# preamp.net
KiCad netlist of a schematic drawn in Altium Designer
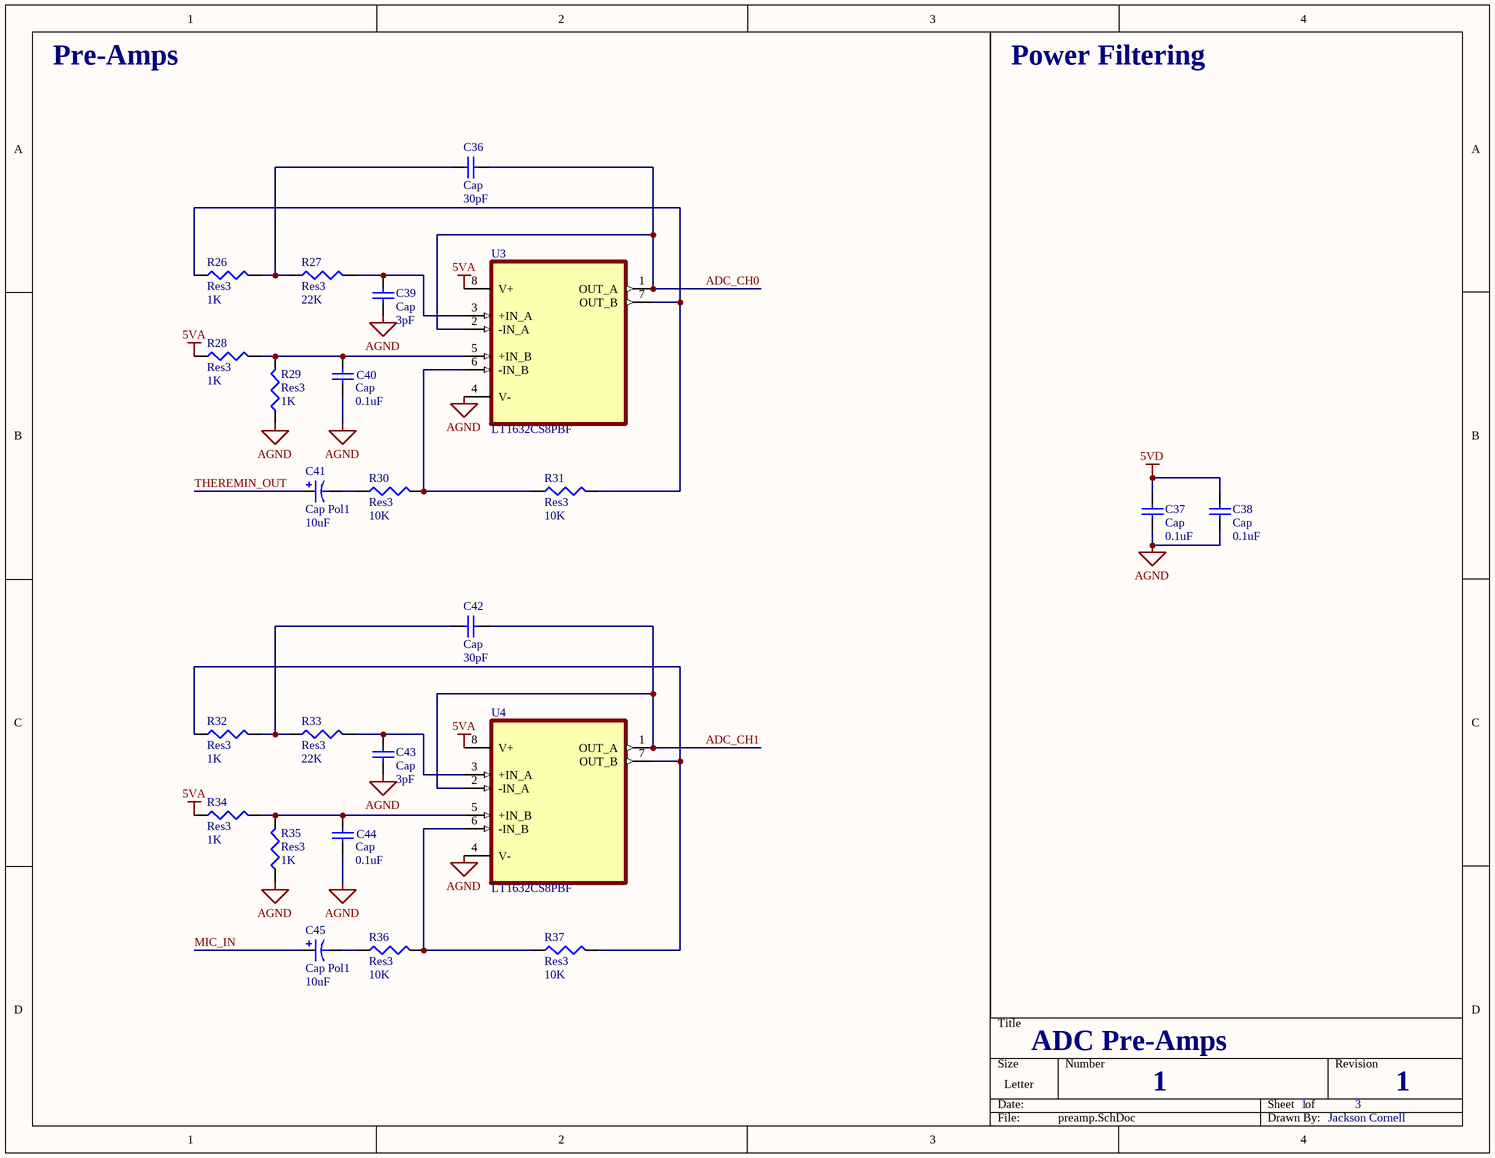
[diagram p0: preamp.SchDoc]

(export (version "E")
  (design (tool "Eeschema 10.0.6"))
  (components
    (comp (ref "C36")
      (value "Cap")
      (footprint "CAPC0805")
      (description "Capacitor")
      (fields (field (name "ALTIUM_VALUE") "30pF") (field (name "PUBLISHER") "Altium Limited"))
      (libsource (lib "Miscellaneous Devices") (part "Cap"))
    )
    (comp (ref "C37")
      (value "Cap")
      (footprint "CAPC0805")
      (description "Capacitor")
      (fields (field (name "ALTIUM_VALUE") "0.1uF") (field (name "PUBLISHER") "Altium Limited"))
      (libsource (lib "Miscellaneous Devices") (part "Cap"))
    )
    (comp (ref "C38")
      (value "Cap")
      (footprint "CAPC0805")
      (description "Capacitor")
      (fields (field (name "ALTIUM_VALUE") "0.1uF") (field (name "PUBLISHER") "Altium Limited"))
      (libsource (lib "Miscellaneous Devices") (part "Cap"))
    )
    (comp (ref "C39")
      (value "Cap")
      (footprint "CAPC0805")
      (description "Capacitor")
      (fields (field (name "ALTIUM_VALUE") "3pF") (field (name "PUBLISHER") "Altium Limited"))
      (libsource (lib "Miscellaneous Devices") (part "Cap"))
    )
    (comp (ref "C40")
      (value "Cap")
      (footprint "CAPC0805")
      (description "Capacitor")
      (fields (field (name "ALTIUM_VALUE") "0.1uF") (field (name "PUBLISHER") "Altium Limited"))
      (libsource (lib "Miscellaneous Devices") (part "Cap"))
    )
    (comp (ref "C41")
      (value "Cap Pol1")
      (footprint "CAPC0805")
      (description "Polarized Capacitor (Radial)")
      (fields (field (name "ALTIUM_VALUE") "10uF") (field (name "PUBLISHER") "Altium Limited"))
      (libsource (lib "Miscellaneous Devices") (part "Cap Pol1"))
    )
    (comp (ref "C42")
      (value "Cap")
      (footprint "CAPC0805")
      (description "Capacitor")
      (fields (field (name "ALTIUM_VALUE") "30pF") (field (name "PUBLISHER") "Altium Limited"))
      (libsource (lib "Miscellaneous Devices") (part "Cap"))
    )
    (comp (ref "C43")
      (value "Cap")
      (footprint "CAPC0805")
      (description "Capacitor")
      (fields (field (name "ALTIUM_VALUE") "3pF") (field (name "PUBLISHER") "Altium Limited"))
      (libsource (lib "Miscellaneous Devices") (part "Cap"))
    )
    (comp (ref "C44")
      (value "Cap")
      (footprint "CAPC0805")
      (description "Capacitor")
      (fields (field (name "ALTIUM_VALUE") "0.1uF") (field (name "PUBLISHER") "Altium Limited"))
      (libsource (lib "Miscellaneous Devices") (part "Cap"))
    )
    (comp (ref "C45")
      (value "Cap Pol1")
      (footprint "RES0805")
      (description "Polarized Capacitor (Radial)")
      (fields (field (name "ALTIUM_VALUE") "10uF") (field (name "PUBLISHER") "Altium Limited"))
      (libsource (lib "Miscellaneous Devices") (part "Cap Pol1"))
    )
    (comp (ref "R26")
      (value "Res3")
      (footprint "RES0805")
      (description "Resistor")
      (fields (field (name "ALTIUM_VALUE") "1K") (field (name "PUBLISHER") "Altium Limited"))
      (libsource (lib "Miscellaneous Devices") (part "Res3"))
    )
    (comp (ref "R27")
      (value "Res3")
      (footprint "RES0805")
      (description "Resistor")
      (fields (field (name "ALTIUM_VALUE") "22K") (field (name "PUBLISHER") "Altium Limited"))
      (libsource (lib "Miscellaneous Devices") (part "Res3"))
    )
    (comp (ref "R28")
      (value "Res3")
      (footprint "RES0805")
      (description "Resistor")
      (fields (field (name "ALTIUM_VALUE") "1K") (field (name "PUBLISHER") "Altium Limited"))
      (libsource (lib "Miscellaneous Devices") (part "Res3"))
    )
    (comp (ref "R29")
      (value "Res3")
      (footprint "RES0805")
      (description "Resistor")
      (fields (field (name "ALTIUM_VALUE") "1K") (field (name "PUBLISHER") "Altium Limited"))
      (libsource (lib "Miscellaneous Devices") (part "Res3"))
    )
    (comp (ref "R30")
      (value "Res3")
      (footprint "RES0805")
      (description "Resistor")
      (fields (field (name "ALTIUM_VALUE") "10K") (field (name "PUBLISHER") "Altium Limited"))
      (libsource (lib "Miscellaneous Devices") (part "Res3"))
    )
    (comp (ref "R31")
      (value "Res3")
      (footprint "RES0805")
      (description "Resistor")
      (fields (field (name "ALTIUM_VALUE") "10K") (field (name "PUBLISHER") "Altium Limited"))
      (libsource (lib "Miscellaneous Devices") (part "Res3"))
    )
    (comp (ref "R32")
      (value "Res3")
      (footprint "RES0805")
      (description "Resistor")
      (fields (field (name "ALTIUM_VALUE") "1K") (field (name "PUBLISHER") "Altium Limited"))
      (libsource (lib "Miscellaneous Devices") (part "Res3"))
    )
    (comp (ref "R33")
      (value "Res3")
      (footprint "RES0805")
      (description "Resistor")
      (fields (field (name "ALTIUM_VALUE") "22K") (field (name "PUBLISHER") "Altium Limited"))
      (libsource (lib "Miscellaneous Devices") (part "Res3"))
    )
    (comp (ref "R34")
      (value "Res3")
      (footprint "RES0805")
      (description "Resistor")
      (fields (field (name "ALTIUM_VALUE") "1K") (field (name "PUBLISHER") "Altium Limited"))
      (libsource (lib "Miscellaneous Devices") (part "Res3"))
    )
    (comp (ref "R35")
      (value "Res3")
      (footprint "RES0805")
      (description "Resistor")
      (fields (field (name "ALTIUM_VALUE") "1K") (field (name "PUBLISHER") "Altium Limited"))
      (libsource (lib "Miscellaneous Devices") (part "Res3"))
    )
    (comp (ref "R36")
      (value "Res3")
      (footprint "RES0805")
      (description "Resistor")
      (fields (field (name "ALTIUM_VALUE") "10K") (field (name "PUBLISHER") "Altium Limited"))
      (libsource (lib "Miscellaneous Devices") (part "Res3"))
    )
    (comp (ref "R37")
      (value "Res3")
      (footprint "RES0805")
      (description "Resistor")
      (fields (field (name "ALTIUM_VALUE") "10K") (field (name "PUBLISHER") "Altium Limited"))
      (libsource (lib "Miscellaneous Devices") (part "Res3"))
    )
    (comp (ref "U3")
      (value "LT1632CS8PBF")
      (footprint "SOIC127P600X175-8N")
      (description "45MHz, 45V/ms, Dual/Quad Rail-to-Rail Input and Output  Precision Op Amps")
      (libsource (lib "LT1632CS8PBF") (part "LT1632CS8PBF"))
    )
    (comp (ref "U4")
      (value "LT1632CS8PBF")
      (footprint "SOIC127P600X175-8N")
      (description "45MHz, 45V/ms, Dual/Quad Rail-to-Rail Input and Output  Precision Op Amps")
      (libsource (lib "LT1632CS8PBF") (part "LT1632CS8PBF"))
    )
  )
  (nets
    (net (code "1") (name "/ADC_CH0") (class "Default")
      (node (ref "C36") (pin "2") (pinfunction "2_2") (pintype "passive"))
      (node (ref "U3") (pin "1") (pinfunction "OUT_A_1") (pintype "output"))
      (node (ref "U3") (pin "2") (pinfunction "-IN_A_2") (pintype "input"))
    )
    (net (code "2") (name "/ADC_CH1") (class "Default")
      (node (ref "C42") (pin "2") (pinfunction "2_2") (pintype "passive"))
      (node (ref "U4") (pin "1") (pinfunction "OUT_A_1") (pintype "output"))
      (node (ref "U4") (pin "2") (pinfunction "-IN_A_2") (pintype "input"))
    )
    (net (code "3") (name "/MIC_IN") (class "Default")
      (node (ref "C45") (pin "1") (pinfunction "1_1") (pintype "passive"))
    )
    (net (code "4") (name "/THEREMIN_OUT") (class "Default")
      (node (ref "C41") (pin "1") (pinfunction "1_1") (pintype "passive"))
    )
    (net (code "5") (name "5VA") (class "Default")
      (node (ref "R28") (pin "1") (pinfunction "1_1") (pintype "passive"))
      (node (ref "R34") (pin "1") (pinfunction "1_1") (pintype "passive"))
      (node (ref "U3") (pin "8") (pinfunction "V+_8") (pintype "power_in"))
      (node (ref "U4") (pin "8") (pinfunction "V+_8") (pintype "power_in"))
    )
    (net (code "6") (name "5VD") (class "Default")
      (node (ref "C37") (pin "2") (pinfunction "2_2") (pintype "passive"))
      (node (ref "C38") (pin "2") (pinfunction "2_2") (pintype "passive"))
    )
    (net (code "7") (name "AGND") (class "Default")
      (node (ref "C37") (pin "1") (pinfunction "1_1") (pintype "passive"))
      (node (ref "C38") (pin "1") (pinfunction "1_1") (pintype "passive"))
      (node (ref "C39") (pin "1") (pinfunction "1_1") (pintype "passive"))
      (node (ref "C40") (pin "1") (pinfunction "1_1") (pintype "passive"))
      (node (ref "C43") (pin "1") (pinfunction "1_1") (pintype "passive"))
      (node (ref "C44") (pin "1") (pinfunction "1_1") (pintype "passive"))
      (node (ref "R29") (pin "1") (pinfunction "1_1") (pintype "passive"))
      (node (ref "R35") (pin "1") (pinfunction "1_1") (pintype "passive"))
      (node (ref "U3") (pin "4") (pinfunction "V-_4") (pintype "power_in"))
      (node (ref "U4") (pin "4") (pinfunction "V-_4") (pintype "power_in"))
    )
    (net (code "8") (name "Net-(C36-Pad1)") (class "Default")
      (node (ref "C36") (pin "1") (pinfunction "1_1") (pintype "passive"))
      (node (ref "R26") (pin "2") (pinfunction "2_2") (pintype "passive"))
      (node (ref "R27") (pin "1") (pinfunction "1_1") (pintype "passive"))
    )
    (net (code "9") (name "Net-(C41-Pad2)") (class "Default")
      (node (ref "C41") (pin "2") (pinfunction "2_2") (pintype "passive"))
      (node (ref "R30") (pin "1") (pinfunction "1_1") (pintype "passive"))
    )
    (net (code "10") (name "Net-(C42-Pad1)") (class "Default")
      (node (ref "C42") (pin "1") (pinfunction "1_1") (pintype "passive"))
      (node (ref "R32") (pin "2") (pinfunction "2_2") (pintype "passive"))
      (node (ref "R33") (pin "1") (pinfunction "1_1") (pintype "passive"))
    )
    (net (code "11") (name "Net-(C45-Pad2)") (class "Default")
      (node (ref "C45") (pin "2") (pinfunction "2_2") (pintype "passive"))
      (node (ref "R36") (pin "1") (pinfunction "1_1") (pintype "passive"))
    )
    (net (code "12") (name "Net-(U3-+IN_A)") (class "Default")
      (node (ref "C39") (pin "2") (pinfunction "2_2") (pintype "passive"))
      (node (ref "R27") (pin "2") (pinfunction "2_2") (pintype "passive"))
      (node (ref "U3") (pin "3") (pinfunction "+IN_A_3") (pintype "input"))
    )
    (net (code "13") (name "Net-(U3-+IN_B)") (class "Default")
      (node (ref "C40") (pin "2") (pinfunction "2_2") (pintype "passive"))
      (node (ref "R28") (pin "2") (pinfunction "2_2") (pintype "passive"))
      (node (ref "R29") (pin "2") (pinfunction "2_2") (pintype "passive"))
      (node (ref "U3") (pin "5") (pinfunction "+IN_B_5") (pintype "input"))
    )
    (net (code "14") (name "Net-(U3--IN_B)") (class "Default")
      (node (ref "R30") (pin "2") (pinfunction "2_2") (pintype "passive"))
      (node (ref "R31") (pin "1") (pinfunction "1_1") (pintype "passive"))
      (node (ref "U3") (pin "6") (pinfunction "-IN_B_6") (pintype "input"))
    )
    (net (code "15") (name "Net-(U3-OUT_B)") (class "Default")
      (node (ref "R26") (pin "1") (pinfunction "1_1") (pintype "passive"))
      (node (ref "R31") (pin "2") (pinfunction "2_2") (pintype "passive"))
      (node (ref "U3") (pin "7") (pinfunction "OUT_B_7") (pintype "output"))
    )
    (net (code "16") (name "Net-(U4-+IN_A)") (class "Default")
      (node (ref "C43") (pin "2") (pinfunction "2_2") (pintype "passive"))
      (node (ref "R33") (pin "2") (pinfunction "2_2") (pintype "passive"))
      (node (ref "U4") (pin "3") (pinfunction "+IN_A_3") (pintype "input"))
    )
    (net (code "17") (name "Net-(U4-+IN_B)") (class "Default")
      (node (ref "C44") (pin "2") (pinfunction "2_2") (pintype "passive"))
      (node (ref "R34") (pin "2") (pinfunction "2_2") (pintype "passive"))
      (node (ref "R35") (pin "2") (pinfunction "2_2") (pintype "passive"))
      (node (ref "U4") (pin "5") (pinfunction "+IN_B_5") (pintype "input"))
    )
    (net (code "18") (name "Net-(U4--IN_B)") (class "Default")
      (node (ref "R36") (pin "2") (pinfunction "2_2") (pintype "passive"))
      (node (ref "R37") (pin "1") (pinfunction "1_1") (pintype "passive"))
      (node (ref "U4") (pin "6") (pinfunction "-IN_B_6") (pintype "input"))
    )
    (net (code "19") (name "Net-(U4-OUT_B)") (class "Default")
      (node (ref "R32") (pin "1") (pinfunction "1_1") (pintype "passive"))
      (node (ref "R37") (pin "2") (pinfunction "2_2") (pintype "passive"))
      (node (ref "U4") (pin "7") (pinfunction "OUT_B_7") (pintype "output"))
    )
  )
)
